# DevBoard.net
KiCad netlist of a schematic drawn in EAGLE
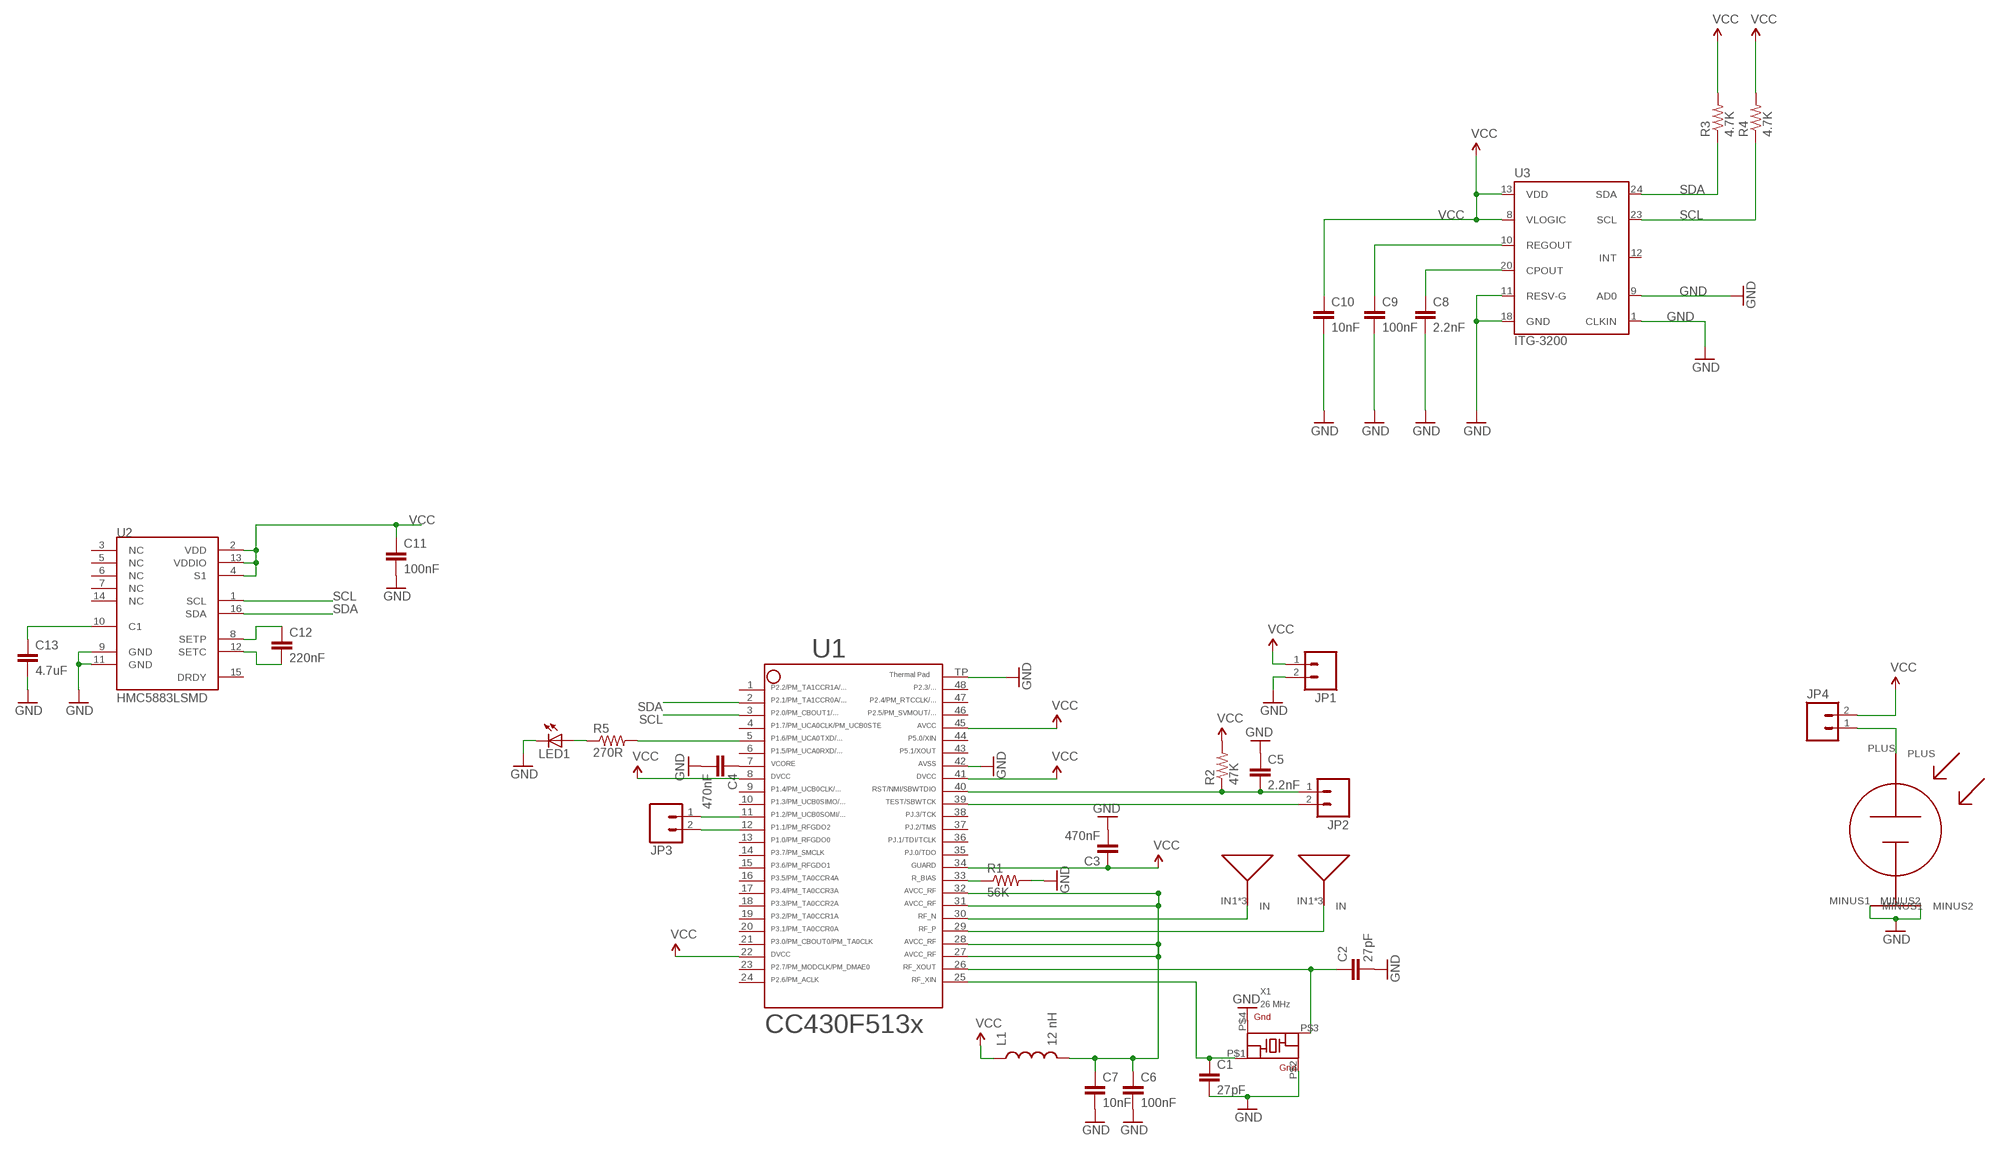
[diagram p0: schematic, sheet 1]

(export (version "E")
  (design (tool "Eeschema 10.0.6"))
  (components
    (comp (ref "ANT-N")
      (value "ANTENNA")
      (footprint "eagle-import:ANTENNA")
      (libsource (lib "eagle-import") (part "ANTENNA"))
    )
    (comp (ref "ANT-P")
      (value "ANTENNA")
      (footprint "eagle-import:ANTENNA")
      (libsource (lib "eagle-import") (part "ANTENNA"))
    )
    (comp (ref "C1")
      (value "27pF")
      (footprint "eagle-import:0603-CAP")
      (libsource (lib "eagle-import") (part "CAP0603-CAP"))
    )
    (comp (ref "C2")
      (value "27pF")
      (footprint "eagle-import:0603-CAP")
      (libsource (lib "eagle-import") (part "CAP0603-CAP"))
    )
    (comp (ref "C3")
      (value "470nF")
      (footprint "eagle-import:0603-CAP")
      (libsource (lib "eagle-import") (part "CAP0603-CAP"))
    )
    (comp (ref "C4")
      (value "470nF")
      (footprint "eagle-import:0603-CAP")
      (libsource (lib "eagle-import") (part "CAP0603-CAP"))
    )
    (comp (ref "C5")
      (value "2.2nF")
      (footprint "eagle-import:0603-CAP")
      (libsource (lib "eagle-import") (part "CAP0603-CAP"))
    )
    (comp (ref "C6")
      (value "100nF")
      (footprint "eagle-import:0603-CAP")
      (libsource (lib "eagle-import") (part "CAP0603-CAP"))
    )
    (comp (ref "C7")
      (value "10nF")
      (footprint "eagle-import:0603-CAP")
      (libsource (lib "eagle-import") (part "CAP0603-CAP"))
    )
    (comp (ref "C8")
      (value "2.2nF")
      (footprint "eagle-import:0603-CAP")
      (libsource (lib "eagle-import") (part "CAP0603-CAP"))
    )
    (comp (ref "C9")
      (value "100nF")
      (footprint "eagle-import:0603-CAP")
      (libsource (lib "eagle-import") (part "CAP0603-CAP"))
    )
    (comp (ref "C10")
      (value "10nF")
      (footprint "eagle-import:0603-CAP")
      (libsource (lib "eagle-import") (part "CAP0603-CAP"))
    )
    (comp (ref "C11")
      (value "100nF")
      (footprint "eagle-import:0603-CAP")
      (libsource (lib "eagle-import") (part "CAP0603-CAP"))
    )
    (comp (ref "C12")
      (value "220nF")
      (footprint "eagle-import:0603-CAP")
      (libsource (lib "eagle-import") (part "CAP0603-CAP"))
    )
    (comp (ref "C13")
      (value "4.7uF")
      (footprint "eagle-import:0603-CAP")
      (libsource (lib "eagle-import") (part "CAP0603-CAP"))
    )
    (comp (ref "JP1")
      (value "M02PTH")
      (footprint "eagle-import:1X02")
      (libsource (lib "eagle-import") (part "M02PTH"))
    )
    (comp (ref "JP2")
      (value "M02PTH")
      (footprint "eagle-import:1X02")
      (libsource (lib "eagle-import") (part "M02PTH"))
    )
    (comp (ref "JP3")
      (value "M02PTH")
      (footprint "eagle-import:1X02")
      (libsource (lib "eagle-import") (part "M02PTH"))
    )
    (comp (ref "JP4")
      (value "M02PTH")
      (footprint "eagle-import:1X02")
      (libsource (lib "eagle-import") (part "M02PTH"))
    )
    (comp (ref "L1")
      (value "12 nH")
      (footprint "eagle-import:0603")
      (libsource (lib "eagle-import") (part "INDUCTOR0603"))
    )
    (comp (ref "LED1")
      (value "LED0603")
      (footprint "eagle-import:LED-0603")
      (libsource (lib "eagle-import") (part "LED0603"))
    )
    (comp (ref "R1")
      (value "56K")
      (footprint "eagle-import:0603-RES")
      (libsource (lib "eagle-import") (part "RESISTOR0603-RES"))
    )
    (comp (ref "R2")
      (value "47K")
      (footprint "eagle-import:0603-RES")
      (libsource (lib "eagle-import") (part "RESISTOR0603-RES"))
    )
    (comp (ref "R3")
      (value "4.7K")
      (footprint "eagle-import:0603-RES")
      (libsource (lib "eagle-import") (part "RESISTOR0603-RES"))
    )
    (comp (ref "R4")
      (value "4.7K")
      (footprint "eagle-import:0603-RES")
      (libsource (lib "eagle-import") (part "RESISTOR0603-RES"))
    )
    (comp (ref "R5")
      (value "270R")
      (footprint "eagle-import:0603-RES")
      (libsource (lib "eagle-import") (part "RESISTOR0603-RES"))
    )
    (comp (ref "S1")
      (value "TASC")
      (footprint "eagle-import:TASC")
      (libsource (lib "eagle-import") (part "TASC"))
    )
    (comp (ref "U1")
      (value "CC430F5137")
      (footprint "eagle-import:RGZ48")
      (libsource (lib "eagle-import") (part "CC430F513X---RGZ48"))
    )
    (comp (ref "U2")
      (value "HMC5883LSMD")
      (footprint "eagle-import:16LPCC")
      (libsource (lib "eagle-import") (part "HMC5883LSMD"))
    )
    (comp (ref "U3")
      (value "ITG-3200")
      (footprint "eagle-import:QFN-24")
      (libsource (lib "eagle-import") (part "ITG-3200"))
    )
    (comp (ref "X1")
      (value "26 MHz")
      (footprint "eagle-import:ABM11_CERAMIC-SMD-CRYSTAL")
      (libsource (lib "eagle-import") (part "ABM11_CERAMIC_SMD_CRYSTALABM11"))
    )
  )
  (nets
    (net (code "1") (name "/SCL") (class "Default")
      (node (ref "R4") (pin "1") (pinfunction "1_1") (pintype "passive"))
      (node (ref "U1") (pin "3") (pinfunction "3_3") (pintype "bidirectional"))
      (node (ref "U2") (pin "1") (pinfunction "SCL_1") (pintype "bidirectional"))
      (node (ref "U3") (pin "23") (pinfunction "SCL_23") (pintype "bidirectional"))
    )
    (net (code "2") (name "/SDA") (class "Default")
      (node (ref "R3") (pin "1") (pinfunction "1_1") (pintype "passive"))
      (node (ref "U1") (pin "2") (pinfunction "2_2") (pintype "bidirectional"))
      (node (ref "U2") (pin "16") (pinfunction "SDA_16") (pintype "bidirectional"))
      (node (ref "U3") (pin "24") (pinfunction "SDA_24") (pintype "bidirectional"))
    )
    (net (code "3") (name "GND") (class "Default")
      (node (ref "C1") (pin "2") (pinfunction "2_2") (pintype "passive"))
      (node (ref "C10") (pin "2") (pinfunction "2_2") (pintype "passive"))
      (node (ref "C11") (pin "2") (pinfunction "2_2") (pintype "passive"))
      (node (ref "C13") (pin "2") (pinfunction "2_2") (pintype "passive"))
      (node (ref "C2") (pin "2") (pinfunction "2_2") (pintype "passive"))
      (node (ref "C3") (pin "2") (pinfunction "2_2") (pintype "passive"))
      (node (ref "C4") (pin "2") (pinfunction "2_2") (pintype "passive"))
      (node (ref "C5") (pin "1") (pinfunction "1_1") (pintype "passive"))
      (node (ref "C6") (pin "2") (pinfunction "2_2") (pintype "passive"))
      (node (ref "C7") (pin "2") (pinfunction "2_2") (pintype "passive"))
      (node (ref "C8") (pin "2") (pinfunction "2_2") (pintype "passive"))
      (node (ref "C9") (pin "2") (pinfunction "2_2") (pintype "passive"))
      (node (ref "JP1") (pin "2") (pinfunction "2_2") (pintype "passive"))
      (node (ref "LED1") (pin "C") (pinfunction "C_C") (pintype "passive"))
      (node (ref "R1") (pin "2") (pinfunction "2_2") (pintype "passive"))
      (node (ref "S1") (pin "MINUS1") (pinfunction "MINUS1_MINUS1") (pintype "power_in"))
      (node (ref "S1") (pin "MINUS2") (pinfunction "MINUS2_MINUS2") (pintype "power_in"))
      (node (ref "U1") (pin "42") (pinfunction "42_42") (pintype "power_in"))
      (node (ref "U1") (pin "TP") (pinfunction "49_TP") (pintype "power_in"))
      (node (ref "U2") (pin "11") (pinfunction "GND_11") (pintype "bidirectional"))
      (node (ref "U2") (pin "9") (pinfunction "GND_9") (pintype "bidirectional"))
      (node (ref "U3") (pin "1") (pinfunction "CLKIN_1") (pintype "bidirectional"))
      (node (ref "U3") (pin "11") (pinfunction "RESV-G_11") (pintype "bidirectional"))
      (node (ref "U3") (pin "18") (pinfunction "GND_18") (pintype "bidirectional"))
      (node (ref "U3") (pin "9") (pinfunction "AD0_9") (pintype "bidirectional"))
      (node (ref "X1") (pin "P$2") (pinfunction "GROUND2_P$2") (pintype "bidirectional"))
      (node (ref "X1") (pin "P$4") (pinfunction "GROUND4_P$4") (pintype "bidirectional"))
    )
    (net (code "4") (name "Net-(ANT-N-IN-PadIN1)") (class "Default")
      (node (ref "ANT-N") (pin "IN1") (pinfunction "IN_IN1") (pintype "bidirectional"))
      (node (ref "ANT-N") (pin "IN2") (pinfunction "IN_IN2") (pintype "bidirectional"))
      (node (ref "ANT-N") (pin "IN3") (pinfunction "IN_IN3") (pintype "bidirectional"))
      (node (ref "U1") (pin "30") (pinfunction "30_30") (pintype "bidirectional"))
    )
    (net (code "5") (name "Net-(ANT-P-IN-PadIN1)") (class "Default")
      (node (ref "ANT-P") (pin "IN1") (pinfunction "IN_IN1") (pintype "bidirectional"))
      (node (ref "ANT-P") (pin "IN2") (pinfunction "IN_IN2") (pintype "bidirectional"))
      (node (ref "ANT-P") (pin "IN3") (pinfunction "IN_IN3") (pintype "bidirectional"))
      (node (ref "U1") (pin "29") (pinfunction "29_29") (pintype "bidirectional"))
    )
    (net (code "6") (name "Net-(C1-Pad1)") (class "Default")
      (node (ref "C1") (pin "1") (pinfunction "1_1") (pintype "passive"))
      (node (ref "U1") (pin "25") (pinfunction "25_25") (pintype "input"))
      (node (ref "X1") (pin "P$1") (pinfunction "P$1_P$1") (pintype "bidirectional"))
    )
    (net (code "7") (name "Net-(C2-Pad1)") (class "Default")
      (node (ref "C2") (pin "1") (pinfunction "1_1") (pintype "passive"))
      (node (ref "U1") (pin "26") (pinfunction "26_26") (pintype "output"))
      (node (ref "X1") (pin "P$3") (pinfunction "P$3_P$3") (pintype "bidirectional"))
    )
    (net (code "8") (name "Net-(C4-Pad1)") (class "Default")
      (node (ref "C4") (pin "1") (pinfunction "1_1") (pintype "passive"))
      (node (ref "U1") (pin "7") (pinfunction "7_7") (pintype "power_in"))
    )
    (net (code "9") (name "Net-(C5-Pad2)") (class "Default")
      (node (ref "C5") (pin "2") (pinfunction "2_2") (pintype "passive"))
      (node (ref "JP2") (pin "1") (pinfunction "1_1") (pintype "passive"))
      (node (ref "R2") (pin "1") (pinfunction "1_1") (pintype "passive"))
      (node (ref "U1") (pin "40") (pinfunction "40_40") (pintype "bidirectional"))
    )
    (net (code "10") (name "Net-(C6-Pad1)") (class "Default")
      (node (ref "C6") (pin "1") (pinfunction "1_1") (pintype "passive"))
      (node (ref "C7") (pin "1") (pinfunction "1_1") (pintype "passive"))
      (node (ref "L1") (pin "2") (pinfunction "2_2") (pintype "passive"))
      (node (ref "U1") (pin "27") (pinfunction "27_27") (pintype "power_in"))
      (node (ref "U1") (pin "28") (pinfunction "28_28") (pintype "bidirectional"))
      (node (ref "U1") (pin "31") (pinfunction "31_31") (pintype "power_in"))
      (node (ref "U1") (pin "32") (pinfunction "32_32") (pintype "power_in"))
    )
    (net (code "11") (name "Net-(JP2-Pad2)") (class "Default")
      (node (ref "JP2") (pin "2") (pinfunction "2_2") (pintype "passive"))
      (node (ref "U1") (pin "39") (pinfunction "39_39") (pintype "input"))
    )
    (net (code "12") (name "Net-(JP3-Pad1)") (class "Default")
      (node (ref "JP3") (pin "1") (pinfunction "1_1") (pintype "passive"))
      (node (ref "U1") (pin "11") (pinfunction "11_11") (pintype "bidirectional"))
    )
    (net (code "13") (name "Net-(JP3-Pad2)") (class "Default")
      (node (ref "JP3") (pin "2") (pinfunction "2_2") (pintype "passive"))
      (node (ref "U1") (pin "12") (pinfunction "12_12") (pintype "bidirectional"))
    )
    (net (code "14") (name "Net-(JP4-Pad1)") (class "Default")
      (node (ref "JP4") (pin "1") (pinfunction "1_1") (pintype "passive"))
      (node (ref "S1") (pin "PLUS") (pinfunction "PLUS_PLUS") (pintype "power_in"))
    )
    (net (code "15") (name "Net-(LED1-PadA)") (class "Default")
      (node (ref "LED1") (pin "A") (pinfunction "A_A") (pintype "passive"))
      (node (ref "R5") (pin "1") (pinfunction "1_1") (pintype "passive"))
    )
    (net (code "16") (name "Net-(R1-Pad1)") (class "Default")
      (node (ref "R1") (pin "1") (pinfunction "1_1") (pintype "passive"))
      (node (ref "U1") (pin "33") (pinfunction "33_33") (pintype "power_in"))
    )
    (net (code "17") (name "Net-(R5-Pad2)") (class "Default")
      (node (ref "R5") (pin "2") (pinfunction "2_2") (pintype "passive"))
      (node (ref "U1") (pin "5") (pinfunction "5_5") (pintype "bidirectional"))
    )
    (net (code "18") (name "Net-(U2-C1)") (class "Default")
      (node (ref "C13") (pin "1") (pinfunction "1_1") (pintype "passive"))
      (node (ref "U2") (pin "10") (pinfunction "C1_10") (pintype "bidirectional"))
    )
    (net (code "19") (name "Net-(U2-SETC)") (class "Default")
      (node (ref "C12") (pin "2") (pinfunction "2_2") (pintype "passive"))
      (node (ref "U2") (pin "12") (pinfunction "SETC_12") (pintype "bidirectional"))
    )
    (net (code "20") (name "Net-(U2-SETP)") (class "Default")
      (node (ref "C12") (pin "1") (pinfunction "1_1") (pintype "passive"))
      (node (ref "U2") (pin "8") (pinfunction "SETP_8") (pintype "bidirectional"))
    )
    (net (code "21") (name "Net-(U3-CPOUT)") (class "Default")
      (node (ref "C8") (pin "1") (pinfunction "1_1") (pintype "passive"))
      (node (ref "U3") (pin "20") (pinfunction "CPOUT_20") (pintype "bidirectional"))
    )
    (net (code "22") (name "Net-(U3-REGOUT)") (class "Default")
      (node (ref "C9") (pin "1") (pinfunction "1_1") (pintype "passive"))
      (node (ref "U3") (pin "10") (pinfunction "REGOUT_10") (pintype "bidirectional"))
    )
    (net (code "23") (name "VCC") (class "Default")
      (node (ref "C10") (pin "1") (pinfunction "1_1") (pintype "passive"))
      (node (ref "C11") (pin "1") (pinfunction "1_1") (pintype "passive"))
      (node (ref "C3") (pin "1") (pinfunction "1_1") (pintype "passive"))
      (node (ref "JP1") (pin "1") (pinfunction "1_1") (pintype "passive"))
      (node (ref "JP4") (pin "2") (pinfunction "2_2") (pintype "passive"))
      (node (ref "L1") (pin "1") (pinfunction "1_1") (pintype "passive"))
      (node (ref "R2") (pin "2") (pinfunction "2_2") (pintype "passive"))
      (node (ref "R3") (pin "2") (pinfunction "2_2") (pintype "passive"))
      (node (ref "R4") (pin "2") (pinfunction "2_2") (pintype "passive"))
      (node (ref "U1") (pin "22") (pinfunction "22_22") (pintype "power_in"))
      (node (ref "U1") (pin "34") (pinfunction "34_34") (pintype "power_in"))
      (node (ref "U1") (pin "41") (pinfunction "41_41") (pintype "power_in"))
      (node (ref "U1") (pin "45") (pinfunction "45_45") (pintype "input"))
      (node (ref "U1") (pin "8") (pinfunction "8_8") (pintype "power_in"))
      (node (ref "U2") (pin "13") (pinfunction "VDDIO_13") (pintype "bidirectional"))
      (node (ref "U2") (pin "2") (pinfunction "VDD_2") (pintype "bidirectional"))
      (node (ref "U2") (pin "4") (pinfunction "S1_4") (pintype "bidirectional"))
      (node (ref "U3") (pin "13") (pinfunction "VDD_13") (pintype "bidirectional"))
      (node (ref "U3") (pin "8") (pinfunction "VLOGIC_8") (pintype "bidirectional"))
    )
    (net (code "24") (name "unconnected-(U1-Pad1)") (class "Default")
      (node (ref "U1") (pin "1") (pinfunction "1_1") (pintype "bidirectional"))
    )
    (net (code "25") (name "unconnected-(U1-Pad4)") (class "Default")
      (node (ref "U1") (pin "4") (pinfunction "4_4") (pintype "bidirectional"))
    )
    (net (code "26") (name "unconnected-(U1-Pad6)") (class "Default")
      (node (ref "U1") (pin "6") (pinfunction "6_6") (pintype "bidirectional"))
    )
    (net (code "27") (name "unconnected-(U1-Pad9)") (class "Default")
      (node (ref "U1") (pin "9") (pinfunction "9_9") (pintype "bidirectional"))
    )
    (net (code "28") (name "unconnected-(U1-Pad10)") (class "Default")
      (node (ref "U1") (pin "10") (pinfunction "10_10") (pintype "bidirectional"))
    )
    (net (code "29") (name "unconnected-(U1-Pad13)") (class "Default")
      (node (ref "U1") (pin "13") (pinfunction "13_13") (pintype "bidirectional"))
    )
    (net (code "30") (name "unconnected-(U1-Pad14)") (class "Default")
      (node (ref "U1") (pin "14") (pinfunction "14_14") (pintype "bidirectional"))
    )
    (net (code "31") (name "unconnected-(U1-Pad15)") (class "Default")
      (node (ref "U1") (pin "15") (pinfunction "15_15") (pintype "bidirectional"))
    )
    (net (code "32") (name "unconnected-(U1-Pad16)") (class "Default")
      (node (ref "U1") (pin "16") (pinfunction "16_16") (pintype "bidirectional"))
    )
    (net (code "33") (name "unconnected-(U1-Pad17)") (class "Default")
      (node (ref "U1") (pin "17") (pinfunction "17_17") (pintype "bidirectional"))
    )
    (net (code "34") (name "unconnected-(U1-Pad18)") (class "Default")
      (node (ref "U1") (pin "18") (pinfunction "18_18") (pintype "bidirectional"))
    )
    (net (code "35") (name "unconnected-(U1-Pad19)") (class "Default")
      (node (ref "U1") (pin "19") (pinfunction "19_19") (pintype "bidirectional"))
    )
    (net (code "36") (name "unconnected-(U1-Pad20)") (class "Default")
      (node (ref "U1") (pin "20") (pinfunction "20_20") (pintype "bidirectional"))
    )
    (net (code "37") (name "unconnected-(U1-Pad21)") (class "Default")
      (node (ref "U1") (pin "21") (pinfunction "21_21") (pintype "bidirectional"))
    )
    (net (code "38") (name "unconnected-(U1-Pad23)") (class "Default")
      (node (ref "U1") (pin "23") (pinfunction "23_23") (pintype "bidirectional"))
    )
    (net (code "39") (name "unconnected-(U1-Pad24)") (class "Default")
      (node (ref "U1") (pin "24") (pinfunction "24_24") (pintype "bidirectional"))
    )
    (net (code "40") (name "unconnected-(U1-Pad35)") (class "Default")
      (node (ref "U1") (pin "35") (pinfunction "35_35") (pintype "bidirectional"))
    )
    (net (code "41") (name "unconnected-(U1-Pad36)") (class "Default")
      (node (ref "U1") (pin "36") (pinfunction "36_36") (pintype "bidirectional"))
    )
    (net (code "42") (name "unconnected-(U1-Pad37)") (class "Default")
      (node (ref "U1") (pin "37") (pinfunction "37_37") (pintype "bidirectional"))
    )
    (net (code "43") (name "unconnected-(U1-Pad38)") (class "Default")
      (node (ref "U1") (pin "38") (pinfunction "38_38") (pintype "bidirectional"))
    )
    (net (code "44") (name "unconnected-(U1-Pad43)") (class "Default")
      (node (ref "U1") (pin "43") (pinfunction "43_43") (pintype "input"))
    )
    (net (code "45") (name "unconnected-(U1-Pad44)") (class "Default")
      (node (ref "U1") (pin "44") (pinfunction "44_44") (pintype "input"))
    )
    (net (code "46") (name "unconnected-(U1-Pad46)") (class "Default")
      (node (ref "U1") (pin "46") (pinfunction "46_46") (pintype "bidirectional"))
    )
    (net (code "47") (name "unconnected-(U1-Pad47)") (class "Default")
      (node (ref "U1") (pin "47") (pinfunction "47_47") (pintype "input"))
    )
    (net (code "48") (name "unconnected-(U1-Pad48)") (class "Default")
      (node (ref "U1") (pin "48") (pinfunction "48_48") (pintype "bidirectional"))
    )
    (net (code "49") (name "unconnected-(U2-DRDY-Pad15)") (class "Default")
      (node (ref "U2") (pin "15") (pinfunction "DRDY_15") (pintype "bidirectional"))
    )
    (net (code "50") (name "unconnected-(U2-NC-Pad3)") (class "Default")
      (node (ref "U2") (pin "3") (pinfunction "NC_3") (pintype "bidirectional"))
    )
    (net (code "51") (name "unconnected-(U2-NC-Pad5)") (class "Default")
      (node (ref "U2") (pin "5") (pinfunction "NC_5") (pintype "bidirectional"))
    )
    (net (code "52") (name "unconnected-(U2-NC-Pad6)") (class "Default")
      (node (ref "U2") (pin "6") (pinfunction "NC_6") (pintype "bidirectional"))
    )
    (net (code "53") (name "unconnected-(U2-NC-Pad7)") (class "Default")
      (node (ref "U2") (pin "7") (pinfunction "NC_7") (pintype "bidirectional"))
    )
    (net (code "54") (name "unconnected-(U2-NC-Pad14)") (class "Default")
      (node (ref "U2") (pin "14") (pinfunction "NC_14") (pintype "bidirectional"))
    )
    (net (code "55") (name "unconnected-(U3-INT-Pad12)") (class "Default")
      (node (ref "U3") (pin "12") (pinfunction "INT_12") (pintype "bidirectional"))
    )
  )
)
